# mega_connector_shield.net
KiCad netlist of a schematic drawn in EAGLE
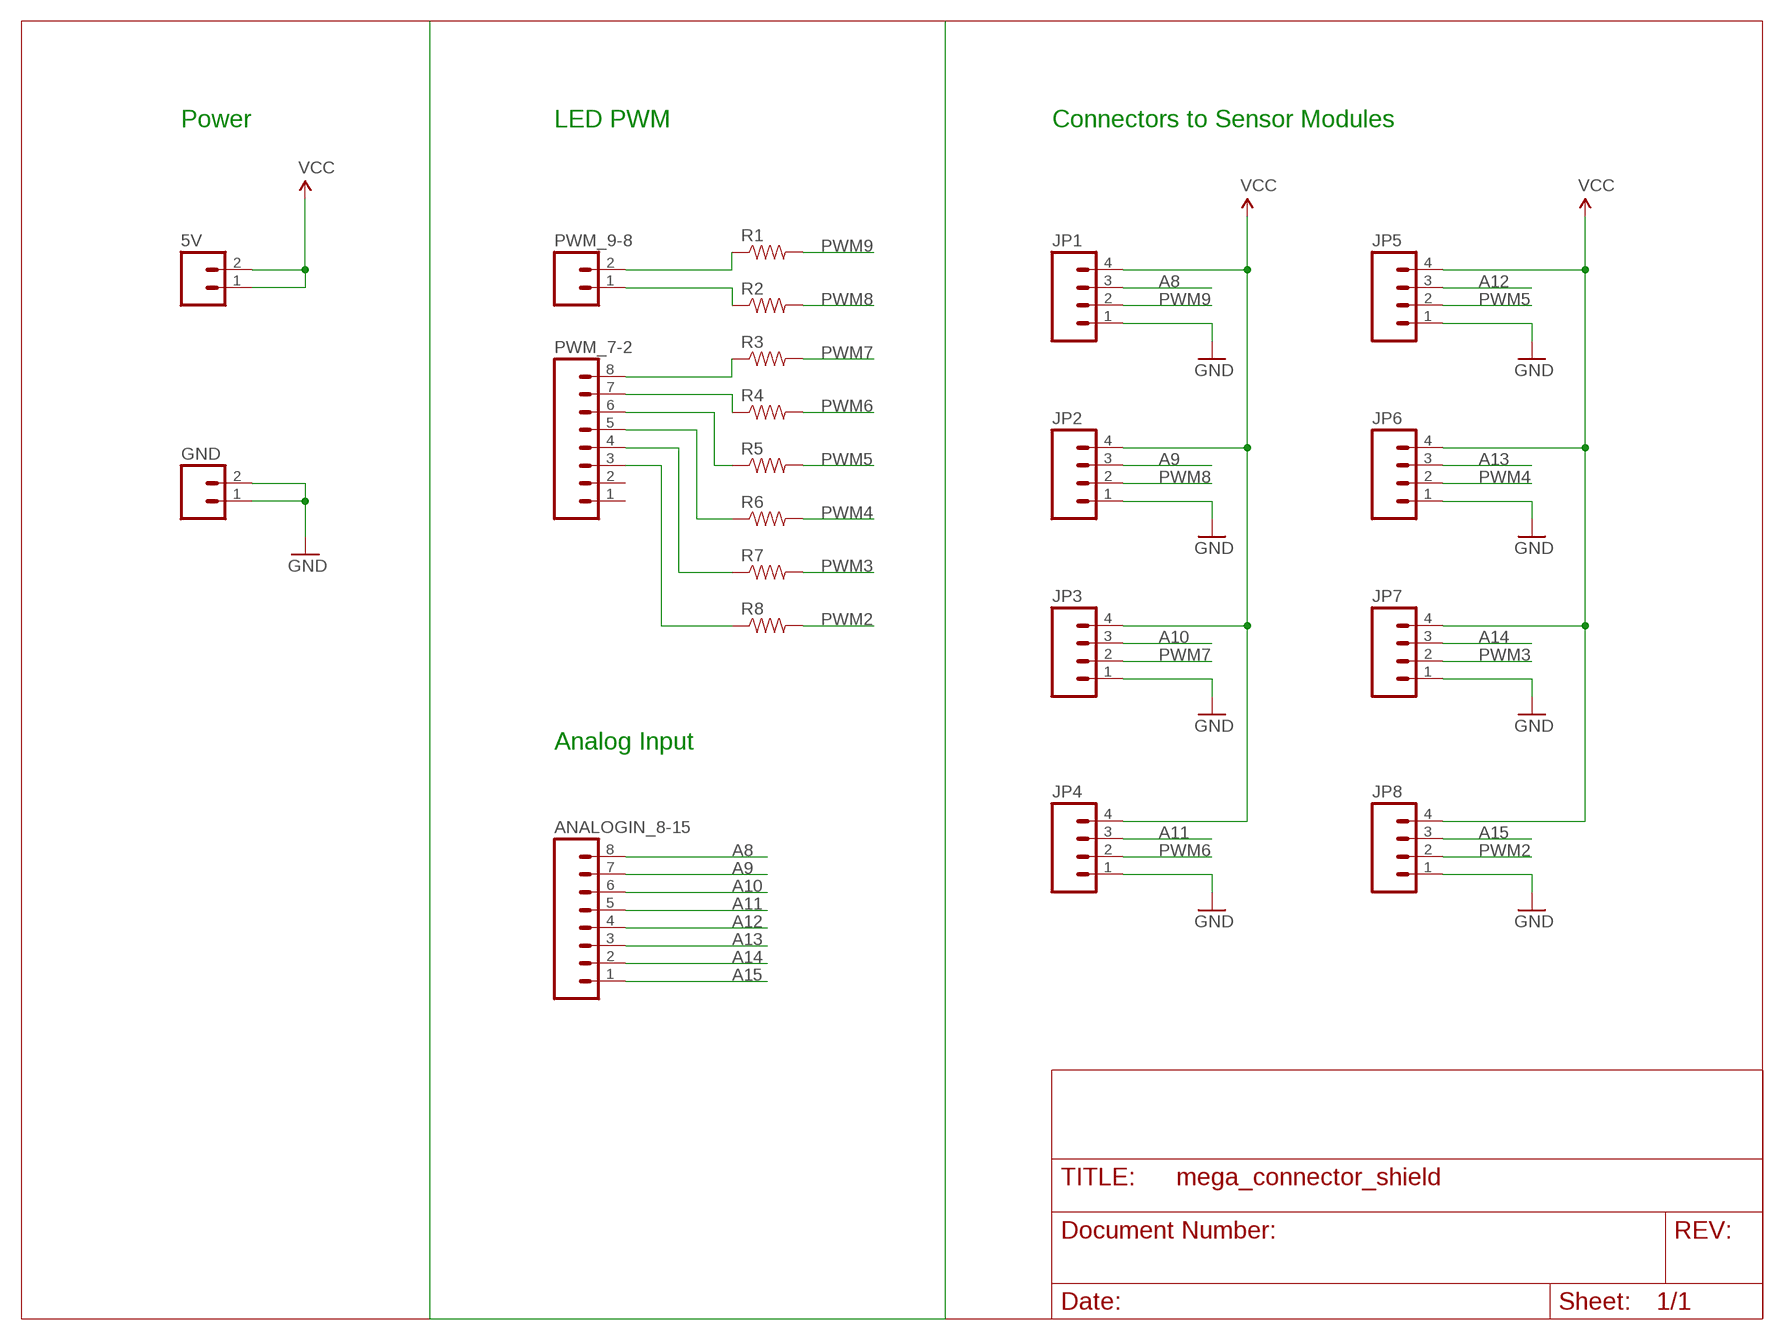
[diagram p0: schematic, sheet 1]

(export (version "E")
  (design (tool "Eeschema 10.0.6"))
  (components
    (comp (ref "5V")
      (value "M02PTH")
      (footprint "eagle-import:1X02")
      (libsource (lib "eagle-import") (part "M02PTH"))
    )
    (comp (ref "ANALOGIN_8-15")
      (value "M08")
      (footprint "eagle-import:1X08_ROUND")
      (libsource (lib "eagle-import") (part "M08"))
    )
    (comp (ref "GND")
      (value "M02PTH")
      (footprint "eagle-import:1X02")
      (libsource (lib "eagle-import") (part "M02PTH"))
    )
    (comp (ref "JP1")
      (value "M04POLAR")
      (footprint "eagle-import:MOLEX-1X4")
      (libsource (lib "eagle-import") (part "M04POLAR"))
    )
    (comp (ref "JP2")
      (value "M04POLAR")
      (footprint "eagle-import:MOLEX-1X4")
      (libsource (lib "eagle-import") (part "M04POLAR"))
    )
    (comp (ref "JP3")
      (value "M04POLAR")
      (footprint "eagle-import:MOLEX-1X4")
      (libsource (lib "eagle-import") (part "M04POLAR"))
    )
    (comp (ref "JP4")
      (value "M04POLAR")
      (footprint "eagle-import:MOLEX-1X4")
      (libsource (lib "eagle-import") (part "M04POLAR"))
    )
    (comp (ref "JP5")
      (value "M04POLAR")
      (footprint "eagle-import:MOLEX-1X4")
      (libsource (lib "eagle-import") (part "M04POLAR"))
    )
    (comp (ref "JP6")
      (value "M04POLAR")
      (footprint "eagle-import:MOLEX-1X4")
      (libsource (lib "eagle-import") (part "M04POLAR"))
    )
    (comp (ref "JP7")
      (value "M04POLAR")
      (footprint "eagle-import:MOLEX-1X4")
      (libsource (lib "eagle-import") (part "M04POLAR"))
    )
    (comp (ref "JP8")
      (value "M04POLAR")
      (footprint "eagle-import:MOLEX-1X4")
      (libsource (lib "eagle-import") (part "M04POLAR"))
    )
    (comp (ref "PWM_7-2")
      (value "M08")
      (footprint "eagle-import:1X08_ROUND")
      (libsource (lib "eagle-import") (part "M08"))
    )
    (comp (ref "PWM_9-8")
      (value "M02PTH")
      (footprint "eagle-import:1X02")
      (libsource (lib "eagle-import") (part "M02PTH"))
    )
    (comp (ref "R1")
      (value "RESISTOR1206")
      (footprint "eagle-import:1206")
      (libsource (lib "eagle-import") (part "RESISTOR1206"))
    )
    (comp (ref "R2")
      (value "RESISTOR1206")
      (footprint "eagle-import:1206")
      (libsource (lib "eagle-import") (part "RESISTOR1206"))
    )
    (comp (ref "R3")
      (value "RESISTOR1206")
      (footprint "eagle-import:1206")
      (libsource (lib "eagle-import") (part "RESISTOR1206"))
    )
    (comp (ref "R4")
      (value "RESISTOR1206")
      (footprint "eagle-import:1206")
      (libsource (lib "eagle-import") (part "RESISTOR1206"))
    )
    (comp (ref "R5")
      (value "RESISTOR1206")
      (footprint "eagle-import:1206")
      (libsource (lib "eagle-import") (part "RESISTOR1206"))
    )
    (comp (ref "R6")
      (value "RESISTOR1206")
      (footprint "eagle-import:1206")
      (libsource (lib "eagle-import") (part "RESISTOR1206"))
    )
    (comp (ref "R7")
      (value "RESISTOR1206")
      (footprint "eagle-import:1206")
      (libsource (lib "eagle-import") (part "RESISTOR1206"))
    )
    (comp (ref "R8")
      (value "RESISTOR1206")
      (footprint "eagle-import:1206")
      (libsource (lib "eagle-import") (part "RESISTOR1206"))
    )
  )
  (nets
    (net (code "1") (name "/A8") (class "Default")
      (node (ref "ANALOGIN_8-15") (pin "8") (pinfunction "8_8") (pintype "passive"))
      (node (ref "JP1") (pin "3") (pinfunction "3_3") (pintype "passive"))
    )
    (net (code "2") (name "/A9") (class "Default")
      (node (ref "ANALOGIN_8-15") (pin "7") (pinfunction "7_7") (pintype "passive"))
      (node (ref "JP2") (pin "3") (pinfunction "3_3") (pintype "passive"))
    )
    (net (code "3") (name "/A10") (class "Default")
      (node (ref "ANALOGIN_8-15") (pin "6") (pinfunction "6_6") (pintype "passive"))
      (node (ref "JP3") (pin "3") (pinfunction "3_3") (pintype "passive"))
    )
    (net (code "4") (name "/A11") (class "Default")
      (node (ref "ANALOGIN_8-15") (pin "5") (pinfunction "5_5") (pintype "passive"))
      (node (ref "JP4") (pin "3") (pinfunction "3_3") (pintype "passive"))
    )
    (net (code "5") (name "/A12") (class "Default")
      (node (ref "ANALOGIN_8-15") (pin "4") (pinfunction "4_4") (pintype "passive"))
      (node (ref "JP5") (pin "3") (pinfunction "3_3") (pintype "passive"))
    )
    (net (code "6") (name "/A13") (class "Default")
      (node (ref "ANALOGIN_8-15") (pin "3") (pinfunction "3_3") (pintype "passive"))
      (node (ref "JP6") (pin "3") (pinfunction "3_3") (pintype "passive"))
    )
    (net (code "7") (name "/A14") (class "Default")
      (node (ref "ANALOGIN_8-15") (pin "2") (pinfunction "2_2") (pintype "passive"))
      (node (ref "JP7") (pin "3") (pinfunction "3_3") (pintype "passive"))
    )
    (net (code "8") (name "/A15") (class "Default")
      (node (ref "ANALOGIN_8-15") (pin "1") (pinfunction "1_1") (pintype "passive"))
      (node (ref "JP8") (pin "3") (pinfunction "3_3") (pintype "passive"))
    )
    (net (code "9") (name "/PWM2") (class "Default")
      (node (ref "JP8") (pin "2") (pinfunction "2_2") (pintype "passive"))
      (node (ref "R8") (pin "2") (pinfunction "2_2") (pintype "passive"))
    )
    (net (code "10") (name "/PWM3") (class "Default")
      (node (ref "JP7") (pin "2") (pinfunction "2_2") (pintype "passive"))
      (node (ref "R7") (pin "2") (pinfunction "2_2") (pintype "passive"))
    )
    (net (code "11") (name "/PWM4") (class "Default")
      (node (ref "JP6") (pin "2") (pinfunction "2_2") (pintype "passive"))
      (node (ref "R6") (pin "2") (pinfunction "2_2") (pintype "passive"))
    )
    (net (code "12") (name "/PWM5") (class "Default")
      (node (ref "JP5") (pin "2") (pinfunction "2_2") (pintype "passive"))
      (node (ref "R5") (pin "2") (pinfunction "2_2") (pintype "passive"))
    )
    (net (code "13") (name "/PWM6") (class "Default")
      (node (ref "JP4") (pin "2") (pinfunction "2_2") (pintype "passive"))
      (node (ref "R4") (pin "2") (pinfunction "2_2") (pintype "passive"))
    )
    (net (code "14") (name "/PWM7") (class "Default")
      (node (ref "JP3") (pin "2") (pinfunction "2_2") (pintype "passive"))
      (node (ref "R3") (pin "2") (pinfunction "2_2") (pintype "passive"))
    )
    (net (code "15") (name "/PWM8") (class "Default")
      (node (ref "JP2") (pin "2") (pinfunction "2_2") (pintype "passive"))
      (node (ref "R2") (pin "2") (pinfunction "2_2") (pintype "passive"))
    )
    (net (code "16") (name "/PWM9") (class "Default")
      (node (ref "JP1") (pin "2") (pinfunction "2_2") (pintype "passive"))
      (node (ref "R1") (pin "2") (pinfunction "2_2") (pintype "passive"))
    )
    (net (code "17") (name "GND") (class "Default")
      (node (ref "GND") (pin "1") (pinfunction "1_1") (pintype "passive"))
      (node (ref "GND") (pin "2") (pinfunction "2_2") (pintype "passive"))
      (node (ref "JP1") (pin "1") (pinfunction "1_1") (pintype "passive"))
      (node (ref "JP2") (pin "1") (pinfunction "1_1") (pintype "passive"))
      (node (ref "JP3") (pin "1") (pinfunction "1_1") (pintype "passive"))
      (node (ref "JP4") (pin "1") (pinfunction "1_1") (pintype "passive"))
      (node (ref "JP5") (pin "1") (pinfunction "1_1") (pintype "passive"))
      (node (ref "JP6") (pin "1") (pinfunction "1_1") (pintype "passive"))
      (node (ref "JP7") (pin "1") (pinfunction "1_1") (pintype "passive"))
      (node (ref "JP8") (pin "1") (pinfunction "1_1") (pintype "passive"))
    )
    (net (code "18") (name "Net-(PWM_7-2-Pad3)") (class "Default")
      (node (ref "PWM_7-2") (pin "3") (pinfunction "3_3") (pintype "passive"))
      (node (ref "R8") (pin "1") (pinfunction "1_1") (pintype "passive"))
    )
    (net (code "19") (name "Net-(PWM_7-2-Pad4)") (class "Default")
      (node (ref "PWM_7-2") (pin "4") (pinfunction "4_4") (pintype "passive"))
      (node (ref "R7") (pin "1") (pinfunction "1_1") (pintype "passive"))
    )
    (net (code "20") (name "Net-(PWM_7-2-Pad5)") (class "Default")
      (node (ref "PWM_7-2") (pin "5") (pinfunction "5_5") (pintype "passive"))
      (node (ref "R6") (pin "1") (pinfunction "1_1") (pintype "passive"))
    )
    (net (code "21") (name "Net-(PWM_7-2-Pad6)") (class "Default")
      (node (ref "PWM_7-2") (pin "6") (pinfunction "6_6") (pintype "passive"))
      (node (ref "R5") (pin "1") (pinfunction "1_1") (pintype "passive"))
    )
    (net (code "22") (name "Net-(PWM_7-2-Pad7)") (class "Default")
      (node (ref "PWM_7-2") (pin "7") (pinfunction "7_7") (pintype "passive"))
      (node (ref "R4") (pin "1") (pinfunction "1_1") (pintype "passive"))
    )
    (net (code "23") (name "Net-(PWM_7-2-Pad8)") (class "Default")
      (node (ref "PWM_7-2") (pin "8") (pinfunction "8_8") (pintype "passive"))
      (node (ref "R3") (pin "1") (pinfunction "1_1") (pintype "passive"))
    )
    (net (code "24") (name "Net-(PWM_9-8-Pad1)") (class "Default")
      (node (ref "PWM_9-8") (pin "1") (pinfunction "1_1") (pintype "passive"))
      (node (ref "R2") (pin "1") (pinfunction "1_1") (pintype "passive"))
    )
    (net (code "25") (name "Net-(PWM_9-8-Pad2)") (class "Default")
      (node (ref "PWM_9-8") (pin "2") (pinfunction "2_2") (pintype "passive"))
      (node (ref "R1") (pin "1") (pinfunction "1_1") (pintype "passive"))
    )
    (net (code "26") (name "VCC") (class "Default")
      (node (ref "5V") (pin "1") (pinfunction "1_1") (pintype "passive"))
      (node (ref "5V") (pin "2") (pinfunction "2_2") (pintype "passive"))
      (node (ref "JP1") (pin "4") (pinfunction "4_4") (pintype "passive"))
      (node (ref "JP2") (pin "4") (pinfunction "4_4") (pintype "passive"))
      (node (ref "JP3") (pin "4") (pinfunction "4_4") (pintype "passive"))
      (node (ref "JP4") (pin "4") (pinfunction "4_4") (pintype "passive"))
      (node (ref "JP5") (pin "4") (pinfunction "4_4") (pintype "passive"))
      (node (ref "JP6") (pin "4") (pinfunction "4_4") (pintype "passive"))
      (node (ref "JP7") (pin "4") (pinfunction "4_4") (pintype "passive"))
      (node (ref "JP8") (pin "4") (pinfunction "4_4") (pintype "passive"))
    )
    (net (code "27") (name "unconnected-(PWM_7-2-Pad1)") (class "Default")
      (node (ref "PWM_7-2") (pin "1") (pinfunction "1_1") (pintype "passive"))
    )
    (net (code "28") (name "unconnected-(PWM_7-2-Pad2)") (class "Default")
      (node (ref "PWM_7-2") (pin "2") (pinfunction "2_2") (pintype "passive"))
    )
  )
)
